# Transmitter.net
KiCad netlist of a schematic drawn in Altium Designer
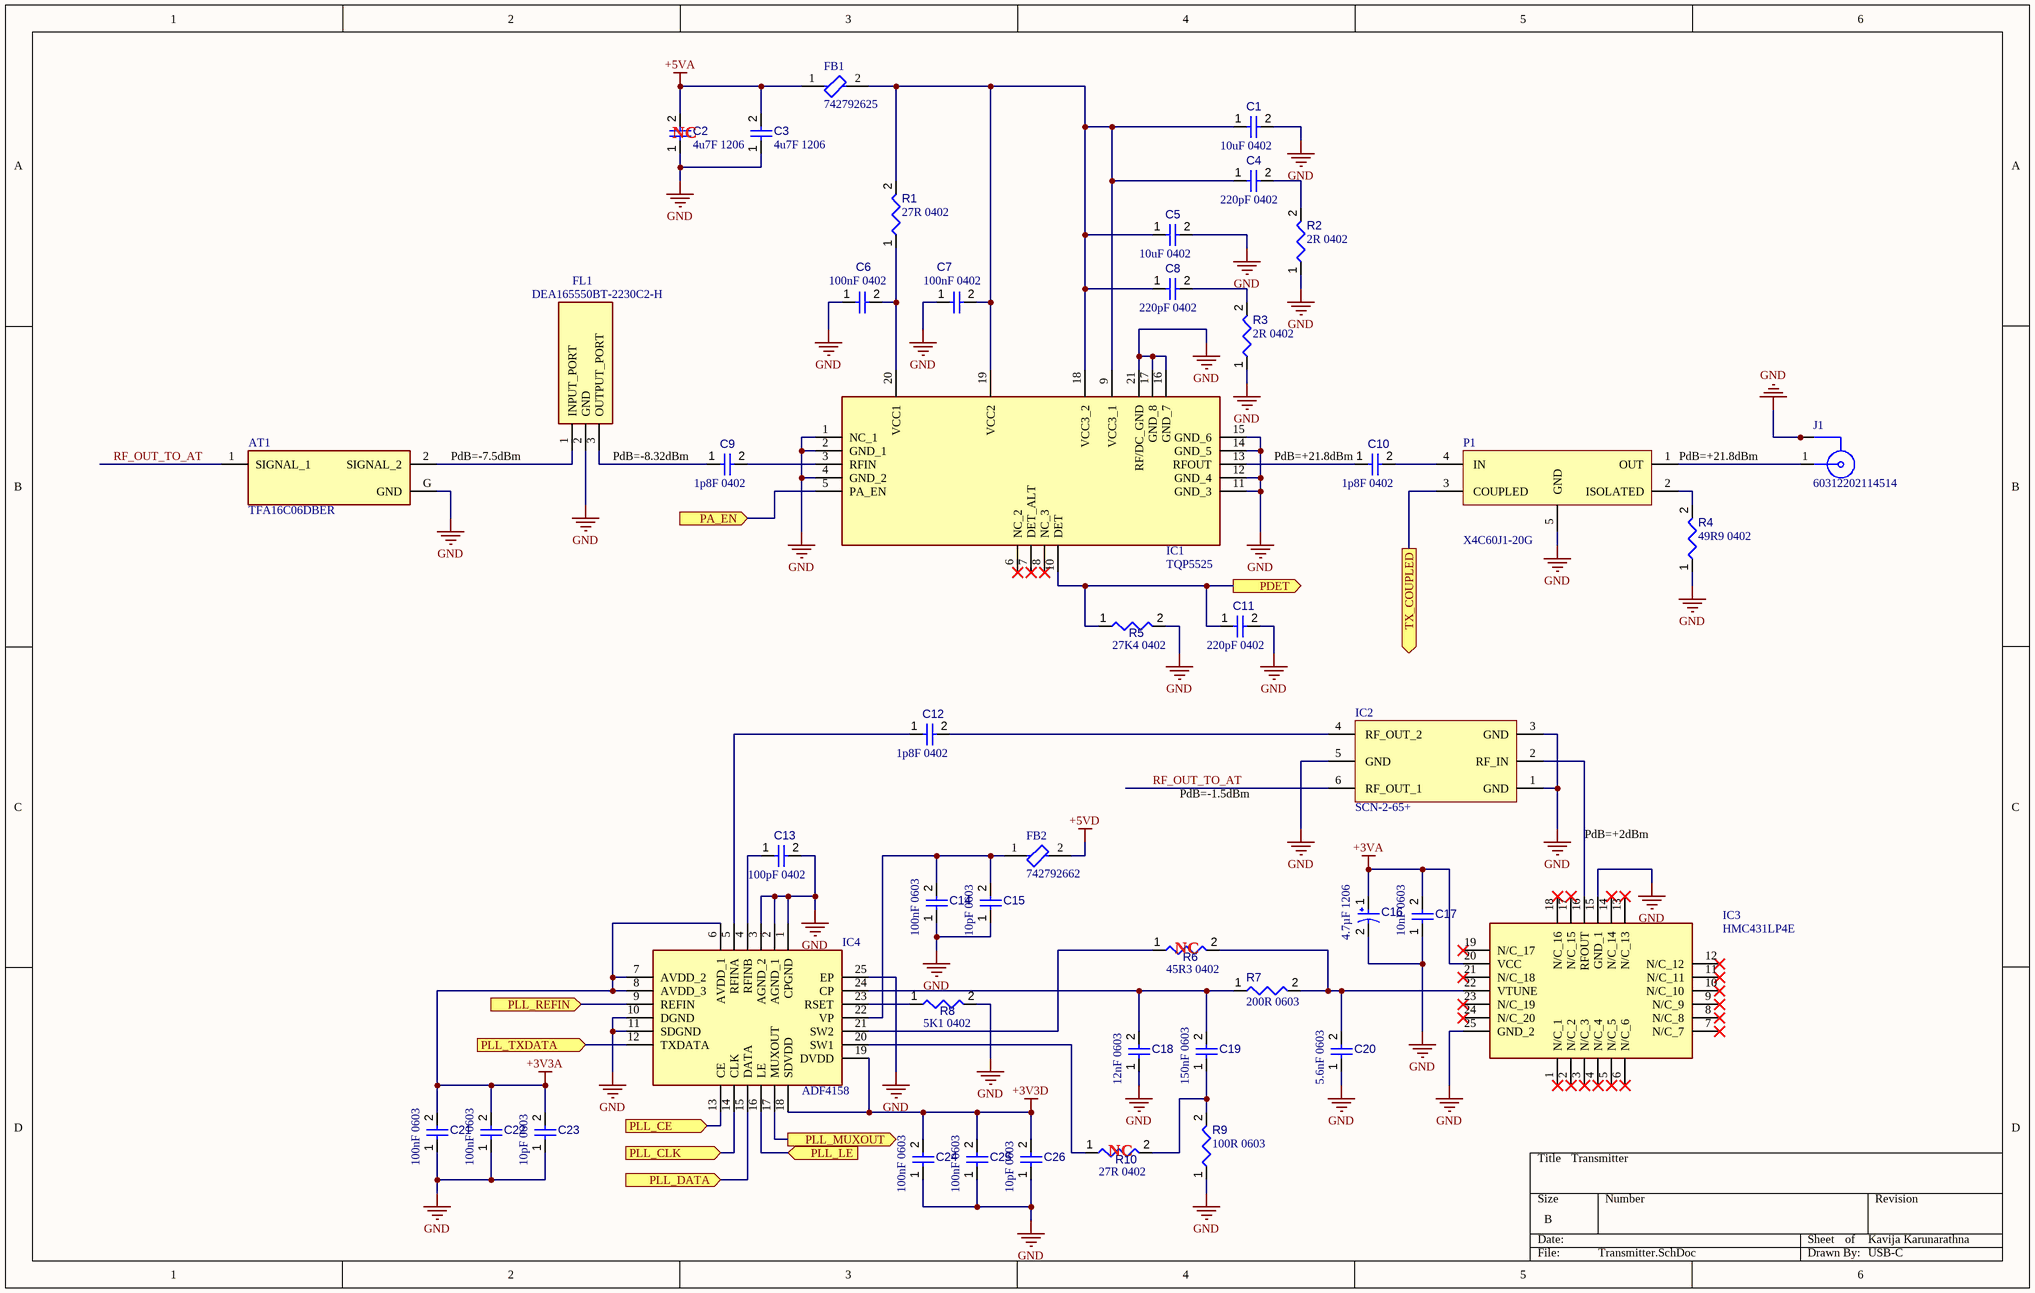
[diagram p0: Transmitter.SchDoc]

(export (version "E")
  (design (tool "Eeschema 10.0.6"))
  (components
    (comp (ref "AT1")
      (value "TFA16C06DBER")
      (footprint "ATTN_TFA16C06DBER")
      (description "RF ATTENUATOR0603 RF ATTENUATOR")
      (fields (field (name "MF") "Ohmite") (field (name "MOUSER PART NO") "588-TFA16C06DBER"))
      (libsource (lib "Kavija Karunarathna") (part "TFA16C06DBER"))
    )
    (comp (ref "C1")
      (value "10uF 0402")
      (footprint "CAPC0402(1005)60_L")
      (fields
        (field (name "TOLERANCE") "20%")
        (field (name "MANUFACTURER PART NO") "04024D106MAT2A")
        (field (name "MOUSER PART NO") "581-04024D106MAT2A")
      )
      (libsource (lib "Kavija Karunarathna") (part "CAP-NP-2"))
    )
    (comp (ref "C2")
      (value "4u7F 1206")
      (footprint "CAPC3216X180X50NL20T25")
      (description "Multilayer Ceramic Capacitors MLCC - SMD/SMT 50V 4.7uF X7R 1206 10% HI CV")
      (fields (field (name "TOLERANCE") "10%") (field (name "MANUFACTURER PART NO") "CC1206KFX7R9BB475"))
      (libsource (lib "Kavija Karunarathna") (part "CAP-NP-2"))
    )
    (comp (ref "C3")
      (value "4u7F 1206")
      (footprint "CAPC3216X180X50NL20T25")
      (description "Multilayer Ceramic Capacitors MLCC - SMD/SMT 50V 4.7uF X7R 1206 10% HI CV")
      (fields (field (name "TOLERANCE") "10%") (field (name "MANUFACTURER PART NO") "CC1206KFX7R9BB475"))
      (libsource (lib "Kavija Karunarathna") (part "CAP-NP-2"))
    )
    (comp (ref "C4")
      (value "220pF 0402")
      (footprint "CAPC0402(1005)60_L")
      (description "Multilayer Ceramic Capacitors MLCC - SMD/SMT VJ 0402 C0G 221 0.1 Ni barrier 50V Unmarked 7\" reel")
      (fields (field (name "TOLERANCE") "20%") (field (name "MANUFACTURER PART NO") "VJ0402A221KXAAC"))
      (libsource (lib "Kavija Karunarathna") (part "CAP-NP-2"))
    )
    (comp (ref "C5")
      (value "10uF 0402")
      (footprint "CAPC0402(1005)60_L")
      (fields
        (field (name "TOLERANCE") "20%")
        (field (name "MANUFACTURER PART NO") "04024D106MAT2A")
        (field (name "MOUSER PART NO") "581-04024D106MAT2A")
      )
      (libsource (lib "Kavija Karunarathna") (part "CAP-NP-2"))
    )
    (comp (ref "C6")
      (value "100nF 0402")
      (footprint "CAPC0402(1005)60_L")
      (description "Multilayer Ceramic Capacitors MLCC - SMD/SMT 25V .1uF X7R 0402 10 % -62C Storage Temp")
      (fields (field (name "TOLERANCE") "20%") (field (name "MANUFACTURER PART NO") "04023C104KAT2A-62"))
      (libsource (lib "Kavija Karunarathna") (part "CAP-NP-2"))
    )
    (comp (ref "C7")
      (value "100nF 0402")
      (footprint "CAPC0402(1005)60_L")
      (description "Multilayer Ceramic Capacitors MLCC - SMD/SMT 25V .1uF X7R 0402 10 % -62C Storage Temp")
      (fields (field (name "TOLERANCE") "20%") (field (name "MANUFACTURER PART NO") "04023C104KAT2A-62"))
      (libsource (lib "Kavija Karunarathna") (part "CAP-NP-2"))
    )
    (comp (ref "C8")
      (value "220pF 0402")
      (footprint "CAPC0402(1005)60_L")
      (description "Multilayer Ceramic Capacitors MLCC - SMD/SMT VJ 0402 C0G 221 0.1 Ni barrier 50V Unmarked 7\" reel")
      (fields (field (name "TOLERANCE") "20%") (field (name "MANUFACTURER PART NO") "VJ0402A221KXAAC"))
      (libsource (lib "Kavija Karunarathna") (part "CAP-NP-2"))
    )
    (comp (ref "C9")
      (value "1p8F 0402")
      (footprint "CAPC0402(1005)60_L")
      (description "Multilayer Ceramic Capacitors MLCC - SMD/SMT 50 V 10 pF C0G 0402 1%")
      (fields (field (name "TOLERANCE") "20%") (field (name "MANUFACTURER PART NO") "GJM1555C1H1R8CB01J"))
      (libsource (lib "Kavija Karunarathna") (part "CAP-NP-2"))
    )
    (comp (ref "C10")
      (value "1p8F 0402")
      (footprint "CAPC0402(1005)60_L")
      (description "Multilayer Ceramic Capacitors MLCC - SMD/SMT 50 V 10 pF C0G 0402 1%")
      (fields (field (name "TOLERANCE") "20%") (field (name "MANUFACTURER PART NO") "GJM1555C1H1R8CB01J"))
      (libsource (lib "Kavija Karunarathna") (part "CAP-NP-2"))
    )
    (comp (ref "C11")
      (value "220pF 0402")
      (footprint "CAPC0402(1005)60_L")
      (description "Multilayer Ceramic Capacitors MLCC - SMD/SMT VJ 0402 C0G 221 0.1 Ni barrier 50V Unmarked 7\" reel")
      (fields (field (name "TOLERANCE") "20%") (field (name "MANUFACTURER PART NO") "VJ0402A221KXAAC"))
      (libsource (lib "Kavija Karunarathna") (part "CAP-NP-2"))
    )
    (comp (ref "C12")
      (value "1p8F 0402")
      (footprint "CAPC0402(1005)60_L")
      (description "Multilayer Ceramic Capacitors MLCC - SMD/SMT 50 V 10 pF C0G 0402 1%")
      (fields (field (name "TOLERANCE") "20%") (field (name "MANUFACTURER PART NO") "GJM1555C1H1R8CB01J"))
      (libsource (lib "Kavija Karunarathna") (part "CAP-NP-2"))
    )
    (comp (ref "C13")
      (value "100pF 0402")
      (footprint "CAPC0402(1005)60_L")
      (description "Chip Capacitor, 47nF +/-20%, 50V, 0402, Thickness 0.6 mm")
      (fields (field (name "TOLERANCE") "20%") (field (name "MANUFACTURER PART NO") "0402X7R101KT2AT"))
      (libsource (lib "Kavija Karunarathna") (part "CAP-NP-2"))
    )
    (comp (ref "C14")
      (value "100nF 0603")
      (footprint "CAPC0603(1608)100_L")
      (description "Chip Capacitor, 1µF +/-0.1%, 25V, 0603, Thickness 1 mm")
      (fields (field (name "TOLERANCE") "20%") (field (name "MANUFACTURER PART NO") "0603X104K250CT"))
      (libsource (lib "Kavija Karunarathna") (part "CAP-NP-2"))
    )
    (comp (ref "C15")
      (value "10pF 0603")
      (footprint "CAPC0603(1608)100_L")
      (description "Chip Capacitor, 1µF +/-0.1%, 25V, 0603, Thickness 1 mm")
      (fields (field (name "TOLERANCE") "20%") (field (name "MANUFACTURER PART NO") "VJ0603A100JXBAP"))
      (libsource (lib "Kavija Karunarathna") (part "CAP-NP-2"))
    )
    (comp (ref "C16")
      (value "4.7µF 1206")
      (footprint "AVX-TAJ-A-2_L")
      (description "Tantalum Capacitors - Solid SMD 20V 4.7uF 1206 10% ESR=4ohms")
      (fields (field (name "MANUFACTURER") "AVX") (field (name "TOLERANCE") "10%"))
      (libsource (lib "Kavija Karunarathna") (part "CAP-P-2"))
    )
    (comp (ref "C17")
      (value "10nF 0603")
      (footprint "CAPC0603(1608)100_L")
      (description "Multilayer Ceramic Capacitors MLCC - SMD/SMT 0603 10nF 16volts X7R 10%")
      (fields (field (name "TOLERANCE") "20%") (field (name "MANUFACTURER PART NO") "VJ0603Y103KXJAC31X"))
      (libsource (lib "Kavija Karunarathna") (part "CAP-NP-2"))
    )
    (comp (ref "C18")
      (value "12nF 0603")
      (footprint "CAPC0603(1608)100_L")
      (description "Multilayer Ceramic Capacitors MLCC - SMD/SMT Cap Cer 0603 12nF 16VDC X8G 1%")
      (fields (field (name "TOLERANCE") "20%") (field (name "MANUFACTURER PART NO") "C0603C123F4TACTU"))
      (libsource (lib "Kavija Karunarathna") (part "CAP-NP-2"))
    )
    (comp (ref "C19")
      (value "150nF 0603")
      (footprint "CAPC0603(1608)100_L")
      (description "Multilayer Ceramic Capacitors MLCC - SMD/SMT 10V .15uF X7R 0603 5 %")
      (fields (field (name "TOLERANCE") "20%") (field (name "MANUFACTURER PART NO") "0603ZC154JAT2A"))
      (libsource (lib "Kavija Karunarathna") (part "CAP-NP-2"))
    )
    (comp (ref "C20")
      (value "5.6nF 0603")
      (footprint "CAPC0603(1608)100_L")
      (description "Chip Capacitor, 1µF +/-0.1%, 25V, 0603, Thickness 1 mm")
      (fields (field (name "TOLERANCE") "20%") (field (name "MANUFACTURER PART NO") "06033C562JAT2A"))
      (libsource (lib "Kavija Karunarathna") (part "CAP-NP-2"))
    )
    (comp (ref "C21")
      (value "100nF 0603")
      (footprint "CAPC0603(1608)100_L")
      (description "Chip Capacitor, 1µF +/-0.1%, 25V, 0603, Thickness 1 mm")
      (fields (field (name "TOLERANCE") "20%") (field (name "MANUFACTURER PART NO") "0603X104K250CT"))
      (libsource (lib "Kavija Karunarathna") (part "CAP-NP-2"))
    )
    (comp (ref "C22")
      (value "100nF 0603")
      (footprint "CAPC0603(1608)100_L")
      (description "Chip Capacitor, 1µF +/-0.1%, 25V, 0603, Thickness 1 mm")
      (fields (field (name "TOLERANCE") "20%") (field (name "MANUFACTURER PART NO") "0603X104K250CT"))
      (libsource (lib "Kavija Karunarathna") (part "CAP-NP-2"))
    )
    (comp (ref "C23")
      (value "10pF 0603")
      (footprint "CAPC0603(1608)100_L")
      (description "Chip Capacitor, 1µF +/-0.1%, 25V, 0603, Thickness 1 mm")
      (fields (field (name "TOLERANCE") "20%") (field (name "MANUFACTURER PART NO") "VJ0603A100JXBAP"))
      (libsource (lib "Kavija Karunarathna") (part "CAP-NP-2"))
    )
    (comp (ref "C24")
      (value "100nF 0603")
      (footprint "CAPC0603(1608)100_L")
      (description "Chip Capacitor, 1µF +/-0.1%, 25V, 0603, Thickness 1 mm")
      (fields (field (name "TOLERANCE") "20%") (field (name "MANUFACTURER PART NO") "0603X104K250CT"))
      (libsource (lib "Kavija Karunarathna") (part "CAP-NP-2"))
    )
    (comp (ref "C25")
      (value "100nF 0603")
      (footprint "CAPC0603(1608)100_L")
      (description "Chip Capacitor, 1µF +/-0.1%, 25V, 0603, Thickness 1 mm")
      (fields (field (name "TOLERANCE") "20%") (field (name "MANUFACTURER PART NO") "0603X104K250CT"))
      (libsource (lib "Kavija Karunarathna") (part "CAP-NP-2"))
    )
    (comp (ref "C26")
      (value "10pF 0603")
      (footprint "CAPC0603(1608)100_L")
      (description "Chip Capacitor, 1µF +/-0.1%, 25V, 0603, Thickness 1 mm")
      (fields (field (name "TOLERANCE") "20%") (field (name "MANUFACTURER PART NO") "VJ0603A100JXBAP"))
      (libsource (lib "Kavija Karunarathna") (part "CAP-NP-2"))
    )
    (comp (ref "FB1")
      (value "742792625")
      (footprint "FB-0603")
      (description "FERRITE BEAD 0603")
      (fields (field (name "MOUSER PART NO") "710-742792625"))
      (libsource (lib "SchLib") (part "742792662-FB"))
    )
    (comp (ref "FB2")
      (value "742792662")
      (footprint "FB-0603")
      (description "FERRITE BEAD 0603")
      (fields (field (name "MOUSER PART NO") "710-742792662"))
      (libsource (lib "SchLib") (part "742792662-FB"))
    )
    (comp (ref "FL1")
      (value "DEA165550BT-2230C2-H")
      (footprint "DEA165550BT-2230C2-H")
      (description "Filter")
      (fields
        (field (name "ARROW PART NUMBER") "DEA165550BT-2322A1-H")
        (field (name "MOUSER PART NO") "810-DEA16555BT223C2H")
      )
      (libsource (lib "SchLib") (part "DEA165550BT-2230C2-H"))
    )
    (comp (ref "IC1")
      (value "TQP5525")
      (footprint "SamacSys:QPA9501TR13")
      (description "Integrated Circuit")
      (fields (field (name "MOUSER PART NO") "772-TQP5525"))
      (libsource (lib "SchLib") (part "QPA9501TR13"))
    )
    (comp (ref "IC2")
      (value "SCN-2-65+")
      (footprint "SCN-2-65+")
      (description "Integrated Circuit")
      (fields (field (name "MOUSER PART NO") "139-SCN-2-65"))
      (libsource (lib "SchLib") (part "SCN-2-65+"))
    )
    (comp (ref "IC3")
      (value "HMC431LP4E")
      (footprint "QFN50P400X400X100-25N")
      (description "Integrated Circuit")
      (fields (field (name "MOUSER PART NO") "584-HMC431LP4E"))
      (libsource (lib "SchLib") (part "HMC431LP4E"))
    )
    (comp (ref "IC4")
      (value "ADF4158")
      (footprint "SamacSys:QFN50P400X400X80-25N-D")
      (description "Integrated Circuit")
      (fields
        (field (name "MANUFACTURER PART NO") "ADF4158CCPZ-RL7")
        (field (name "MOUSER PART NO") "584-ADF4158CCPZ")
      )
      (libsource (lib "SchLib") (part "ADF4158CCPZ-RL7"))
    )
    (comp (ref "J1")
      (value "60312202114514")
      (footprint "60312202114514")
      (fields
        (field (name "MF") "{'manufacturer': u'~{W}xfcrth Elektronik'}")
        (field (name "MOUSER PART NO") "710-60312202114514")
      )
      (libsource (lib "Kavija Karunarathna") (part "60312202114514"))
    )
    (comp (ref "P1")
      (value "X4C60J1-20G")
      (footprint "X4C60J1-20G")
      (fields (field (name "MOUSER PART NO") "620-X4C60J1-20G"))
      (libsource (lib "SchLib") (part "X4C60J1-20G"))
    )
    (comp (ref "R1")
      (value "27R 0402")
      (footprint "RESC0402(1005)_L")
      (description "Thick Film Resistors - SMD 1/10 Watt 5.1Kohms 1%")
      (fields (field (name "TOLERANCE") "1%") (field (name "POWER") "100mW"))
      (libsource (lib "Kavija Karunarathna") (part "383KR2F"))
    )
    (comp (ref "R2")
      (value "2R 0402")
      (footprint "RESC0402(1005)_L")
      (description "Thick Film Resistors - SMD 2 Ohms 50 V 200 mW (1/5 W) 1 mmx0.5 mmx0.35 mm - 55 C+ 155 C")
      (fields (field (name "TOLERANCE") "1%") (field (name "POWER") "100mW"))
      (libsource (lib "Kavija Karunarathna") (part "383KR2F"))
    )
    (comp (ref "R3")
      (value "2R 0402")
      (footprint "RESC0402(1005)_L")
      (description "Thick Film Resistors - SMD 2 Ohms 50 V 200 mW (1/5 W) 1 mmx0.5 mmx0.35 mm - 55 C+ 155 C")
      (fields (field (name "TOLERANCE") "1%") (field (name "POWER") "100mW"))
      (libsource (lib "Kavija Karunarathna") (part "383KR2F"))
    )
    (comp (ref "R4")
      (value "49R9 0402")
      (footprint "RESC0402(1005)_L")
      (description "Thin Film Resistors - SMD 49.9 OHM .1% 50PPM 1/16W")
      (fields (field (name "TOLERANCE") "1%") (field (name "POWER") "100mW"))
      (libsource (lib "Kavija Karunarathna") (part "383KR2F"))
    )
    (comp (ref "R5")
      (value "27K4 0402")
      (footprint "RESC0402(1005)_L")
      (description "Thin Film Resistors - SMD 0402 0.1% 15ppm 27.4Kohm AEC-Q200")
      (fields (field (name "TOLERANCE") "1%") (field (name "POWER") "100mW"))
      (libsource (lib "Kavija Karunarathna") (part "383KR2F"))
    )
    (comp (ref "R6")
      (value "45R3 0402")
      (footprint "RESC0402(1005)_L")
      (description "Thick Film Resistors - SMD 1/10 Watt 5.1Kohms 1%")
      (fields (field (name "TOLERANCE") "1%") (field (name "POWER") "100mW"))
      (libsource (lib "Kavija Karunarathna") (part "383KR2F"))
    )
    (comp (ref "R7")
      (value "200R 0603")
      (footprint "RESC0603(1608)_L")
      (description "Thick Film Resistors - SMD General Purpose Chip Resistor 0603, 200Ohms, 1%, 1/10W")
      (fields (field (name "POWER") "100mW") (field (name "TOLERANCE") "5%"))
      (libsource (lib "Kavija Karunarathna") (part "120R3J"))
    )
    (comp (ref "R8")
      (value "5K1 0402")
      (footprint "RESC0402(1005)_L")
      (description "Thick Film Resistors - SMD 1/10 Watt 5.1Kohms 1%")
      (fields (field (name "TOLERANCE") "1%") (field (name "POWER") "100mW"))
      (libsource (lib "Kavija Karunarathna") (part "383KR2F"))
    )
    (comp (ref "R9")
      (value "100R 0603")
      (footprint "RESC0603(1608)_L")
      (description "Thick Film Resistors - SMD WRIS-RSKS 100 Ohms 1 % 0.1 W 0603 AEC-Q200")
      (fields (field (name "POWER") "100mW") (field (name "TOLERANCE") "5%"))
      (libsource (lib "Kavija Karunarathna") (part "120R3J"))
    )
    (comp (ref "R10")
      (value "27R 0402")
      (footprint "RESC0402(1005)_L")
      (description "Thick Film Resistors - SMD 1/10 Watt 5.1Kohms 1%")
      (fields (field (name "TOLERANCE") "1%") (field (name "POWER") "100mW"))
      (libsource (lib "Kavija Karunarathna") (part "383KR2F"))
    )
  )
  (nets
    (net (code "1") (name "+3V3A") (class "Default")
      (node (ref "C21") (pin "2") (pinfunction "2_2") (pintype "passive"))
      (node (ref "C22") (pin "2") (pinfunction "2_2") (pintype "passive"))
      (node (ref "C23") (pin "2") (pinfunction "2_2") (pintype "passive"))
      (node (ref "IC4") (pin "6") (pinfunction "AVDD_1_6") (pintype "passive"))
      (node (ref "IC4") (pin "7") (pinfunction "AVDD_2_7") (pintype "passive"))
      (node (ref "IC4") (pin "8") (pinfunction "AVDD_3_8") (pintype "passive"))
    )
    (net (code "2") (name "+3V3D") (class "Default")
      (node (ref "C24") (pin "2") (pinfunction "2_2") (pintype "passive"))
      (node (ref "C25") (pin "2") (pinfunction "2_2") (pintype "passive"))
      (node (ref "C26") (pin "2") (pinfunction "2_2") (pintype "passive"))
      (node (ref "IC4") (pin "18") (pinfunction "SDVDD_18") (pintype "passive"))
      (node (ref "IC4") (pin "19") (pinfunction "DVDD_19") (pintype "passive"))
    )
    (net (code "3") (name "+3VA") (class "Default")
      (node (ref "C16") (pin "1") (pinfunction "1_1") (pintype "passive"))
      (node (ref "C17") (pin "2") (pinfunction "2_2") (pintype "passive"))
      (node (ref "IC3") (pin "20") (pinfunction "VCC_20") (pintype "passive"))
    )
    (net (code "4") (name "+5VA") (class "Default")
      (node (ref "C2") (pin "2") (pinfunction "2_2") (pintype "passive"))
      (node (ref "C3") (pin "2") (pinfunction "2_2") (pintype "passive"))
      (node (ref "FB1") (pin "1") (pinfunction "1_1") (pintype "passive"))
    )
    (net (code "5") (name "+5VD") (class "Default")
      (node (ref "FB2") (pin "2") (pinfunction "2_2") (pintype "passive"))
    )
    (net (code "6") (name "/PA_EN") (class "Default")
      (node (ref "IC1") (pin "5") (pinfunction "PA_EN_5") (pintype "passive"))
    )
    (net (code "7") (name "/PDET") (class "Default")
      (node (ref "C11") (pin "1") (pinfunction "1_1") (pintype "passive"))
      (node (ref "IC1") (pin "10") (pinfunction "DET_10") (pintype "passive"))
      (node (ref "R5") (pin "1") (pinfunction "1_1") (pintype "passive"))
    )
    (net (code "8") (name "/PLL_CE") (class "Default")
      (node (ref "IC4") (pin "13") (pinfunction "CE_13") (pintype "passive"))
    )
    (net (code "9") (name "/PLL_CLK") (class "Default")
      (node (ref "IC4") (pin "14") (pinfunction "CLK_14") (pintype "passive"))
    )
    (net (code "10") (name "/PLL_DATA") (class "Default")
      (node (ref "IC4") (pin "15") (pinfunction "DATA_15") (pintype "passive"))
    )
    (net (code "11") (name "/PLL_LE") (class "Default")
      (node (ref "IC4") (pin "16") (pinfunction "LE_16") (pintype "passive"))
    )
    (net (code "12") (name "/PLL_MUXOUT") (class "Default")
      (node (ref "IC4") (pin "17") (pinfunction "MUXOUT_17") (pintype "passive"))
    )
    (net (code "13") (name "/PLL_REFIN") (class "Default")
      (node (ref "IC4") (pin "9") (pinfunction "REFIN_9") (pintype "passive"))
    )
    (net (code "14") (name "/PLL_TXDATA") (class "Default")
      (node (ref "IC4") (pin "12") (pinfunction "TXDATA_12") (pintype "passive"))
    )
    (net (code "15") (name "/RF_OUT_TO_AT") (class "Default")
      (node (ref "AT1") (pin "1") (pinfunction "SIGNAL_1_1") (pintype "passive"))
      (node (ref "IC2") (pin "6") (pinfunction "_RF_OUT_1_6") (pintype "passive"))
    )
    (net (code "16") (name "/TX_COUPLED") (class "Default")
      (node (ref "P1") (pin "3") (pinfunction "_COUPLED_3") (pintype "passive"))
    )
    (net (code "17") (name "GND") (class "Default")
      (node (ref "AT1") (pin "G") (pinfunction "GND_G") (pintype "power_in"))
      (node (ref "C1") (pin "2") (pinfunction "2_2") (pintype "passive"))
      (node (ref "C11") (pin "2") (pinfunction "2_2") (pintype "passive"))
      (node (ref "C13") (pin "2") (pinfunction "2_2") (pintype "passive"))
      (node (ref "C14") (pin "1") (pinfunction "1_1") (pintype "passive"))
      (node (ref "C15") (pin "1") (pinfunction "1_1") (pintype "passive"))
      (node (ref "C16") (pin "2") (pinfunction "2_2") (pintype "passive"))
      (node (ref "C17") (pin "1") (pinfunction "1_1") (pintype "passive"))
      (node (ref "C18") (pin "1") (pinfunction "1_1") (pintype "passive"))
      (node (ref "C2") (pin "1") (pinfunction "1_1") (pintype "passive"))
      (node (ref "C20") (pin "1") (pinfunction "1_1") (pintype "passive"))
      (node (ref "C21") (pin "1") (pinfunction "1_1") (pintype "passive"))
      (node (ref "C22") (pin "1") (pinfunction "1_1") (pintype "passive"))
      (node (ref "C23") (pin "1") (pinfunction "1_1") (pintype "passive"))
      (node (ref "C24") (pin "1") (pinfunction "1_1") (pintype "passive"))
      (node (ref "C25") (pin "1") (pinfunction "1_1") (pintype "passive"))
      (node (ref "C26") (pin "1") (pinfunction "1_1") (pintype "passive"))
      (node (ref "C3") (pin "1") (pinfunction "1_1") (pintype "passive"))
      (node (ref "C5") (pin "2") (pinfunction "2_2") (pintype "passive"))
      (node (ref "C6") (pin "1") (pinfunction "1_1") (pintype "passive"))
      (node (ref "C7") (pin "1") (pinfunction "1_1") (pintype "passive"))
      (node (ref "FL1") (pin "2") (pinfunction "GND_2") (pintype "passive"))
      (node (ref "IC1") (pin "1") (pinfunction "NC_1_1") (pintype "passive"))
      (node (ref "IC1") (pin "11") (pinfunction "GND_3_11") (pintype "passive"))
      (node (ref "IC1") (pin "12") (pinfunction "GND_4_12") (pintype "passive"))
      (node (ref "IC1") (pin "14") (pinfunction "GND_5_14") (pintype "passive"))
      (node (ref "IC1") (pin "15") (pinfunction "GND_6_15") (pintype "passive"))
      (node (ref "IC1") (pin "16") (pinfunction "GND_7_16") (pintype "passive"))
      (node (ref "IC1") (pin "17") (pinfunction "GND_8_17") (pintype "passive"))
      (node (ref "IC1") (pin "2") (pinfunction "GND_1_2") (pintype "passive"))
      (node (ref "IC1") (pin "21") (pinfunction "RF/DC_GND_21") (pintype "passive"))
      (node (ref "IC1") (pin "4") (pinfunction "GND_2_4") (pintype "passive"))
      (node (ref "IC2") (pin "1") (pinfunction "_GND_1") (pintype "passive"))
      (node (ref "IC2") (pin "3") (pinfunction "_GND_3") (pintype "passive"))
      (node (ref "IC2") (pin "5") (pinfunction "_GND_5") (pintype "passive"))
      (node (ref "IC3") (pin "15") (pinfunction "GND_1_15") (pintype "passive"))
      (node (ref "IC3") (pin "25") (pinfunction "GND_2_25") (pintype "passive"))
      (node (ref "IC4") (pin "1") (pinfunction "CPGND_1") (pintype "passive"))
      (node (ref "IC4") (pin "10") (pinfunction "DGND_10") (pintype "passive"))
      (node (ref "IC4") (pin "11") (pinfunction "SDGND_11") (pintype "passive"))
      (node (ref "IC4") (pin "2") (pinfunction "AGND_1_2") (pintype "passive"))
      (node (ref "IC4") (pin "25") (pinfunction "EP_25") (pintype "passive"))
      (node (ref "IC4") (pin "3") (pinfunction "AGND_2_3") (pintype "passive"))
      (node (ref "J1") (pin "2") (pinfunction "2_2") (pintype "passive"))
      (node (ref "J1") (pin "3") (pinfunction "2_3") (pintype "passive"))
      (node (ref "J1") (pin "4") (pinfunction "2_4") (pintype "passive"))
      (node (ref "J1") (pin "5") (pinfunction "2_5") (pintype "passive"))
      (node (ref "P1") (pin "5") (pinfunction "_GND_5") (pintype "passive"))
      (node (ref "R2") (pin "1") (pinfunction "1_1") (pintype "passive"))
      (node (ref "R3") (pin "1") (pinfunction "1_1") (pintype "passive"))
      (node (ref "R4") (pin "1") (pinfunction "1_1") (pintype "passive"))
      (node (ref "R5") (pin "2") (pinfunction "2_2") (pintype "passive"))
      (node (ref "R8") (pin "2") (pinfunction "2_2") (pintype "passive"))
      (node (ref "R9") (pin "1") (pinfunction "1_1") (pintype "passive"))
    )
    (net (code "18") (name "Net-(AT1-SIGNAL_2)") (class "Default")
      (node (ref "AT1") (pin "2") (pinfunction "SIGNAL_2_2") (pintype "passive"))
      (node (ref "FL1") (pin "1") (pinfunction "INPUT_PORT_1") (pintype "passive"))
    )
    (net (code "19") (name "Net-(C4-Pad2)") (class "Default")
      (node (ref "C4") (pin "2") (pinfunction "2_2") (pintype "passive"))
      (node (ref "R2") (pin "2") (pinfunction "2_2") (pintype "passive"))
    )
    (net (code "20") (name "Net-(C8-Pad2)") (class "Default")
      (node (ref "C8") (pin "2") (pinfunction "2_2") (pintype "passive"))
      (node (ref "R3") (pin "2") (pinfunction "2_2") (pintype "passive"))
    )
    (net (code "21") (name "Net-(C19-Pad1)") (class "Default")
      (node (ref "C19") (pin "1") (pinfunction "1_1") (pintype "passive"))
      (node (ref "R10") (pin "2") (pinfunction "2_2") (pintype "passive"))
      (node (ref "R9") (pin "2") (pinfunction "2_2") (pintype "passive"))
    )
    (net (code "22") (name "Net-(FL1-OUTPUT_PORT)") (class "Default")
      (node (ref "C9") (pin "1") (pinfunction "1_1") (pintype "passive"))
      (node (ref "FL1") (pin "3") (pinfunction "OUTPUT_PORT_3") (pintype "passive"))
    )
    (net (code "23") (name "Net-(IC1-RFIN)") (class "Default")
      (node (ref "C9") (pin "2") (pinfunction "2_2") (pintype "passive"))
      (node (ref "IC1") (pin "3") (pinfunction "RFIN_3") (pintype "passive"))
    )
    (net (code "24") (name "Net-(IC1-RFOUT)") (class "Default")
      (node (ref "C10") (pin "1") (pinfunction "1_1") (pintype "passive"))
      (node (ref "IC1") (pin "13") (pinfunction "RFOUT_13") (pintype "passive"))
    )
    (net (code "25") (name "Net-(IC1-VCC1)") (class "Default")
      (node (ref "C6") (pin "2") (pinfunction "2_2") (pintype "passive"))
      (node (ref "IC1") (pin "20") (pinfunction "VCC1_20") (pintype "passive"))
      (node (ref "R1") (pin "1") (pinfunction "1_1") (pintype "passive"))
    )
    (net (code "26") (name "Net-(IC1-VCC2)") (class "Default")
      (node (ref "C1") (pin "1") (pinfunction "1_1") (pintype "passive"))
      (node (ref "C4") (pin "1") (pinfunction "1_1") (pintype "passive"))
      (node (ref "C5") (pin "1") (pinfunction "1_1") (pintype "passive"))
      (node (ref "C7") (pin "2") (pinfunction "2_2") (pintype "passive"))
      (node (ref "C8") (pin "1") (pinfunction "1_1") (pintype "passive"))
      (node (ref "FB1") (pin "2") (pinfunction "2_2") (pintype "passive"))
      (node (ref "IC1") (pin "18") (pinfunction "VCC3_2_18") (pintype "passive"))
      (node (ref "IC1") (pin "19") (pinfunction "VCC2_19") (pintype "passive"))
      (node (ref "IC1") (pin "9") (pinfunction "VCC3_1_9") (pintype "passive"))
      (node (ref "R1") (pin "2") (pinfunction "2_2") (pintype "passive"))
    )
    (net (code "27") (name "Net-(IC2-_RF_IN)") (class "Default")
      (node (ref "IC2") (pin "2") (pinfunction "_RF_IN_2") (pintype "passive"))
      (node (ref "IC3") (pin "16") (pinfunction "RFOUT_16") (pintype "passive"))
    )
    (net (code "28") (name "Net-(IC2-_RF_OUT_2)") (class "Default")
      (node (ref "C12") (pin "2") (pinfunction "2_2") (pintype "passive"))
      (node (ref "IC2") (pin "4") (pinfunction "_RF_OUT_2_4") (pintype "passive"))
    )
    (net (code "29") (name "Net-(IC3-VTUNE)") (class "Default")
      (node (ref "C20") (pin "2") (pinfunction "2_2") (pintype "passive"))
      (node (ref "IC3") (pin "22") (pinfunction "VTUNE_22") (pintype "passive"))
      (node (ref "R6") (pin "2") (pinfunction "2_2") (pintype "passive"))
      (node (ref "R7") (pin "2") (pinfunction "2_2") (pintype "passive"))
    )
    (net (code "30") (name "Net-(IC4-CP)") (class "Default")
      (node (ref "C18") (pin "2") (pinfunction "2_2") (pintype "passive"))
      (node (ref "C19") (pin "2") (pinfunction "2_2") (pintype "passive"))
      (node (ref "IC4") (pin "24") (pinfunction "CP_24") (pintype "passive"))
      (node (ref "R7") (pin "1") (pinfunction "1_1") (pintype "passive"))
    )
    (net (code "31") (name "Net-(IC4-RFINA)") (class "Default")
      (node (ref "C12") (pin "1") (pinfunction "1_1") (pintype "passive"))
      (node (ref "IC4") (pin "5") (pinfunction "RFINA_5") (pintype "passive"))
    )
    (net (code "32") (name "Net-(IC4-RFINB)") (class "Default")
      (node (ref "C13") (pin "1") (pinfunction "1_1") (pintype "passive"))
      (node (ref "IC4") (pin "4") (pinfunction "RFINB_4") (pintype "passive"))
    )
    (net (code "33") (name "Net-(IC4-RSET)") (class "Default")
      (node (ref "IC4") (pin "23") (pinfunction "RSET_23") (pintype "passive"))
      (node (ref "R8") (pin "1") (pinfunction "1_1") (pintype "passive"))
    )
    (net (code "34") (name "Net-(IC4-SW1)") (class "Default")
      (node (ref "IC4") (pin "20") (pinfunction "SW1_20") (pintype "passive"))
      (node (ref "R10") (pin "1") (pinfunction "1_1") (pintype "passive"))
    )
    (net (code "35") (name "Net-(IC4-SW2)") (class "Default")
      (node (ref "IC4") (pin "21") (pinfunction "SW2_21") (pintype "passive"))
      (node (ref "R6") (pin "1") (pinfunction "1_1") (pintype "passive"))
    )
    (net (code "36") (name "Net-(IC4-VP)") (class "Default")
      (node (ref "C14") (pin "2") (pinfunction "2_2") (pintype "passive"))
      (node (ref "C15") (pin "2") (pinfunction "2_2") (pintype "passive"))
      (node (ref "FB2") (pin "1") (pinfunction "1_1") (pintype "passive"))
      (node (ref "IC4") (pin "22") (pinfunction "VP_22") (pintype "passive"))
    )
    (net (code "37") (name "Net-(P1-_IN)") (class "Default")
      (node (ref "C10") (pin "2") (pinfunction "2_2") (pintype "passive"))
      (node (ref "P1") (pin "4") (pinfunction "_IN_4") (pintype "passive"))
    )
    (net (code "38") (name "Net-(P1-_ISOLATED)") (class "Default")
      (node (ref "P1") (pin "2") (pinfunction "_ISOLATED_2") (pintype "passive"))
      (node (ref "R4") (pin "2") (pinfunction "2_2") (pintype "passive"))
    )
    (net (code "39") (name "Net-(P1-_OUT)") (class "Default")
      (node (ref "J1") (pin "1") (pinfunction "1_1") (pintype "passive"))
      (node (ref "P1") (pin "1") (pinfunction "_OUT_1") (pintype "passive"))
    )
    (net (code "40") (name "unconnected-(IC1-DET_ALT-Pad7)") (class "Default")
      (node (ref "IC1") (pin "7") (pinfunction "DET_ALT_7") (pintype "passive+no_connect"))
    )
    (net (code "41") (name "unconnected-(IC1-NC_2-Pad6)") (class "Default")
      (node (ref "IC1") (pin "6") (pinfunction "NC_2_6") (pintype "passive+no_connect"))
    )
    (net (code "42") (name "unconnected-(IC1-NC_3-Pad8)") (class "Default")
      (node (ref "IC1") (pin "8") (pinfunction "NC_3_8") (pintype "passive+no_connect"))
    )
    (net (code "43") (name "unconnected-(IC3-N{slash}C_1-Pad1)") (class "Default")
      (node (ref "IC3") (pin "1") (pinfunction "N/C_1_1") (pintype "passive+no_connect"))
    )
    (net (code "44") (name "unconnected-(IC3-N{slash}C_2-Pad2)") (class "Default")
      (node (ref "IC3") (pin "2") (pinfunction "N/C_2_2") (pintype "passive+no_connect"))
    )
    (net (code "45") (name "unconnected-(IC3-N{slash}C_3-Pad3)") (class "Default")
      (node (ref "IC3") (pin "3") (pinfunction "N/C_3_3") (pintype "passive+no_connect"))
    )
    (net (code "46") (name "unconnected-(IC3-N{slash}C_4-Pad4)") (class "Default")
      (node (ref "IC3") (pin "4") (pinfunction "N/C_4_4") (pintype "passive+no_connect"))
    )
    (net (code "47") (name "unconnected-(IC3-N{slash}C_5-Pad5)") (class "Default")
      (node (ref "IC3") (pin "5") (pinfunction "N/C_5_5") (pintype "passive+no_connect"))
    )
    (net (code "48") (name "unconnected-(IC3-N{slash}C_6-Pad6)") (class "Default")
      (node (ref "IC3") (pin "6") (pinfunction "N/C_6_6") (pintype "passive+no_connect"))
    )
    (net (code "49") (name "unconnected-(IC3-N{slash}C_7-Pad7)") (class "Default")
      (node (ref "IC3") (pin "7") (pinfunction "N/C_7_7") (pintype "passive+no_connect"))
    )
    (net (code "50") (name "unconnected-(IC3-N{slash}C_8-Pad8)") (class "Default")
      (node (ref "IC3") (pin "8") (pinfunction "N/C_8_8") (pintype "passive+no_connect"))
    )
    (net (code "51") (name "unconnected-(IC3-N{slash}C_9-Pad9)") (class "Default")
      (node (ref "IC3") (pin "9") (pinfunction "N/C_9_9") (pintype "passive+no_connect"))
    )
    (net (code "52") (name "unconnected-(IC3-N{slash}C_10-Pad10)") (class "Default")
      (node (ref "IC3") (pin "10") (pinfunction "N/C_10_10") (pintype "passive+no_connect"))
    )
    (net (code "53") (name "unconnected-(IC3-N{slash}C_11-Pad11)") (class "Default")
      (node (ref "IC3") (pin "11") (pinfunction "N/C_11_11") (pintype "passive+no_connect"))
    )
    (net (code "54") (name "unconnected-(IC3-N{slash}C_12-Pad12)") (class "Default")
      (node (ref "IC3") (pin "12") (pinfunction "N/C_12_12") (pintype "passive+no_connect"))
    )
    (net (code "55") (name "unconnected-(IC3-N{slash}C_13-Pad13)") (class "Default")
      (node (ref "IC3") (pin "13") (pinfunction "N/C_13_13") (pintype "passive+no_connect"))
    )
    (net (code "56") (name "unconnected-(IC3-N{slash}C_14-Pad14)") (class "Default")
      (node (ref "IC3") (pin "14") (pinfunction "N/C_14_14") (pintype "passive+no_connect"))
    )
    (net (code "57") (name "unconnected-(IC3-N{slash}C_15-Pad17)") (class "Default")
      (node (ref "IC3") (pin "17") (pinfunction "N/C_15_17") (pintype "passive+no_connect"))
    )
    (net (code "58") (name "unconnected-(IC3-N{slash}C_16-Pad18)") (class "Default")
      (node (ref "IC3") (pin "18") (pinfunction "N/C_16_18") (pintype "passive+no_connect"))
    )
    (net (code "59") (name "unconnected-(IC3-N{slash}C_17-Pad19)") (class "Default")
      (node (ref "IC3") (pin "19") (pinfunction "N/C_17_19") (pintype "passive+no_connect"))
    )
    (net (code "60") (name "unconnected-(IC3-N{slash}C_18-Pad21)") (class "Default")
      (node (ref "IC3") (pin "21") (pinfunction "N/C_18_21") (pintype "passive+no_connect"))
    )
    (net (code "61") (name "unconnected-(IC3-N{slash}C_19-Pad23)") (class "Default")
      (node (ref "IC3") (pin "23") (pinfunction "N/C_19_23") (pintype "passive+no_connect"))
    )
    (net (code "62") (name "unconnected-(IC3-N{slash}C_20-Pad24)") (class "Default")
      (node (ref "IC3") (pin "24") (pinfunction "N/C_20_24") (pintype "passive+no_connect"))
    )
  )
)
